# fpga_gtp.net
KiCad netlist of a schematic drawn in Altium Designer
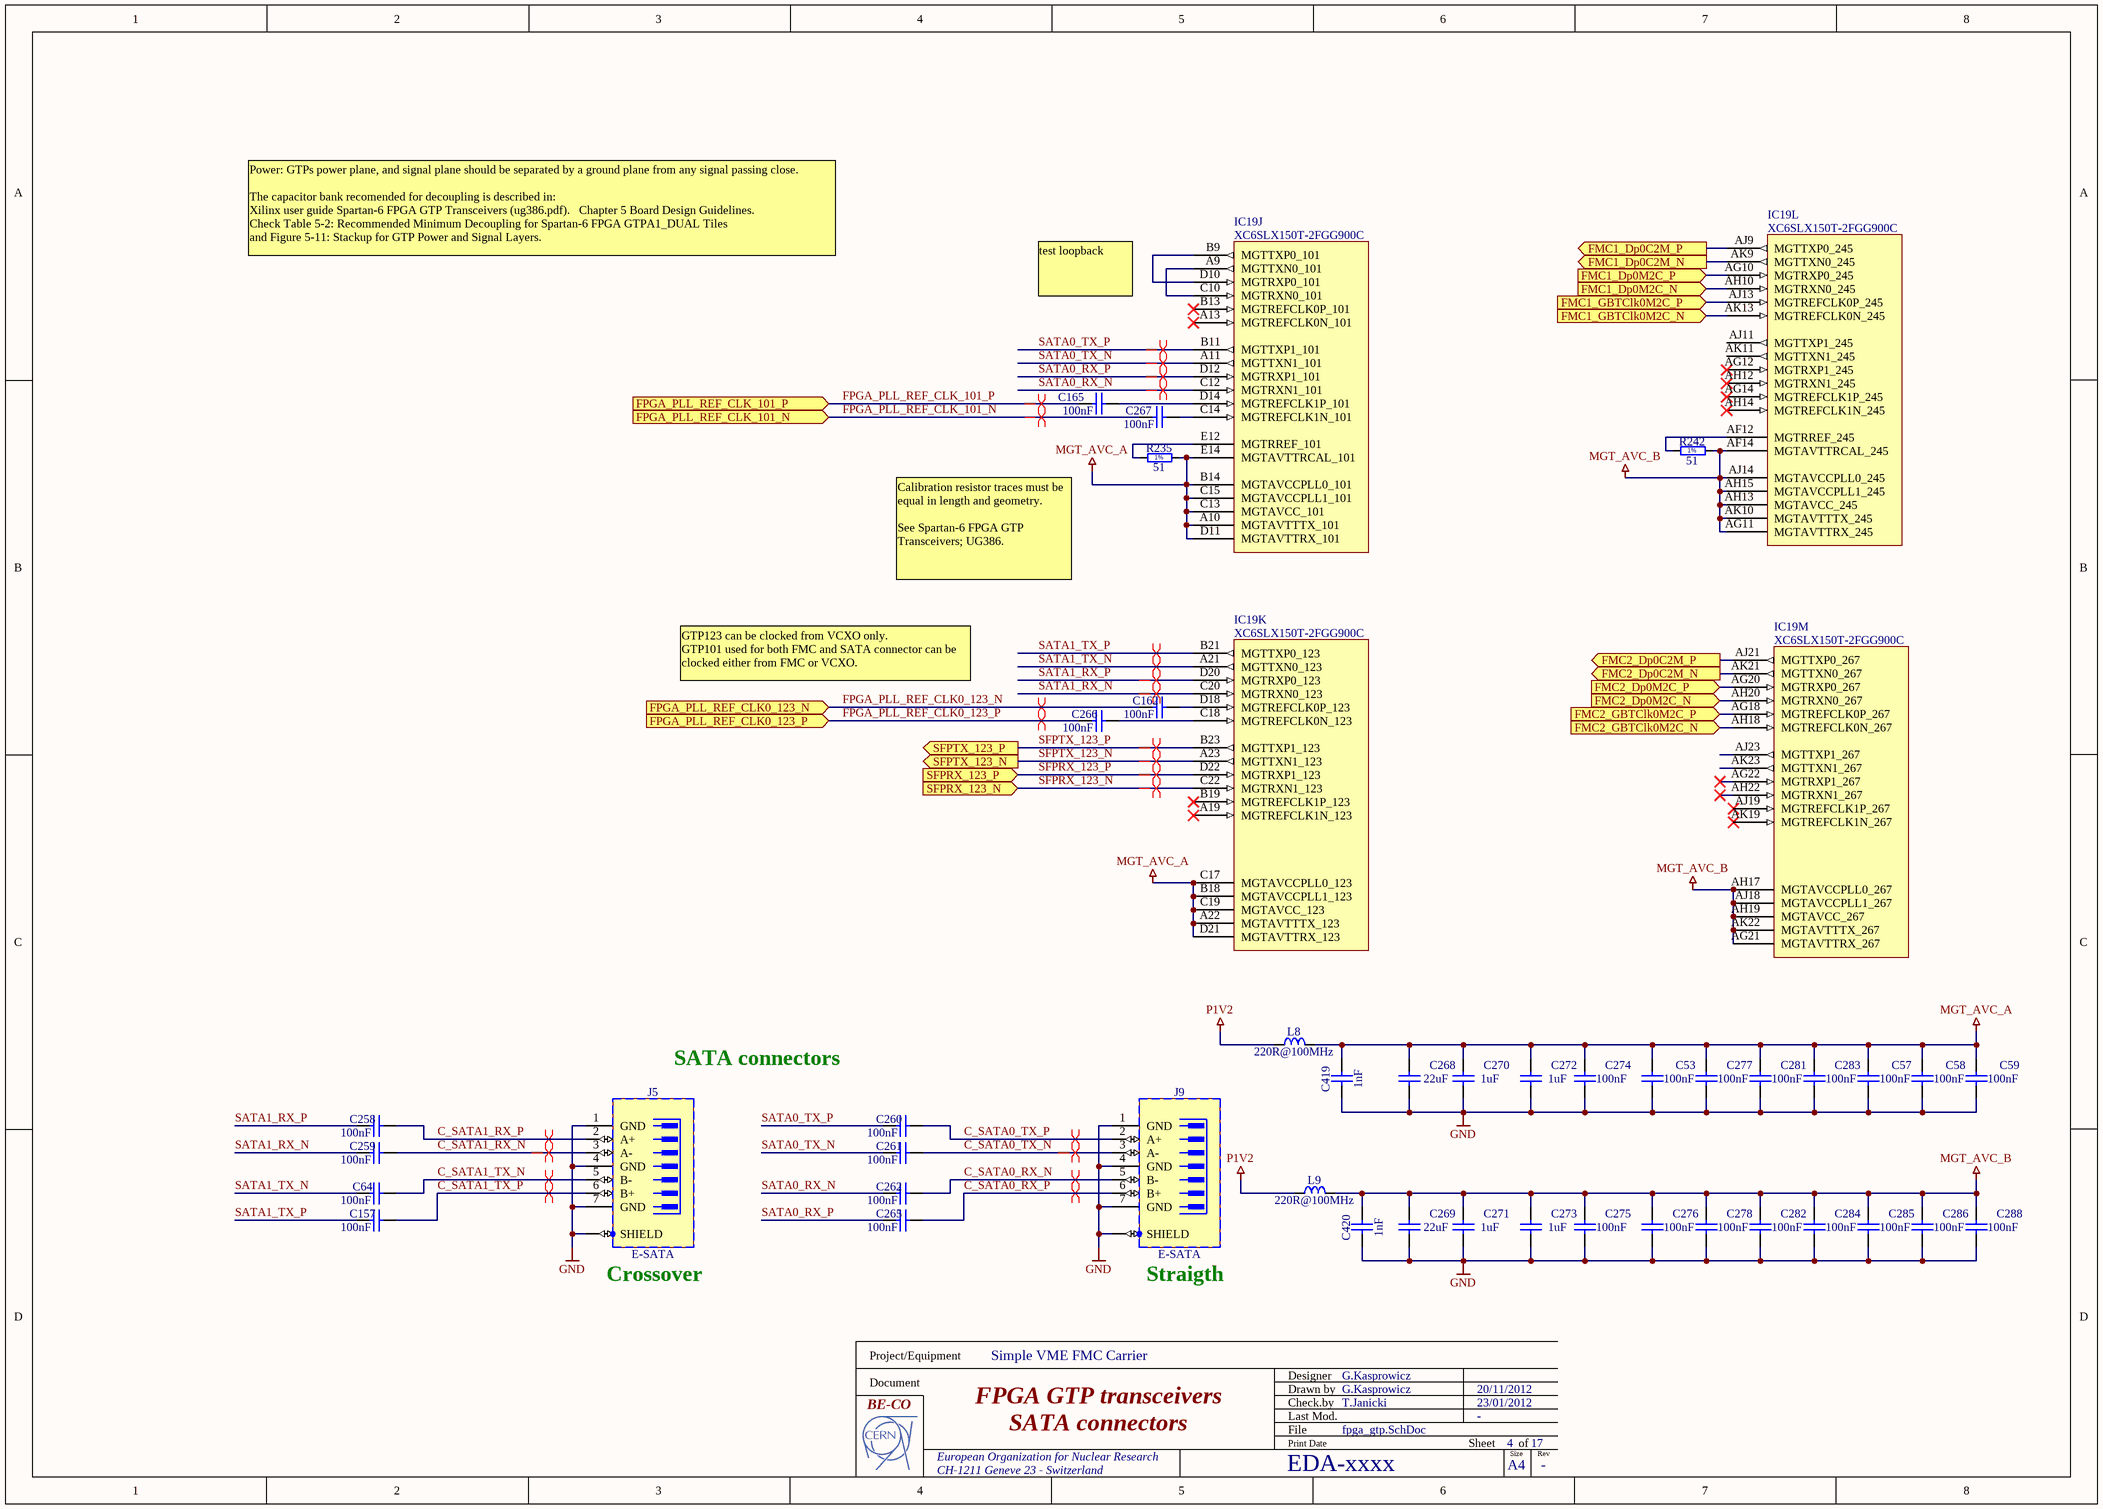
[diagram p0: fpga_gtp.SchDoc]

(export (version "E")
  (design (tool "Eeschema 10.0.6"))
  (components
    (comp (ref "C53")
      (value "100nF")
      (footprint "CAPC1005X55N")
      (description "Non-polarised capacitor")
      (fields
        (field (name "PART NUMBER") "CC0402_100NF_16V_10%_X7R")
        (field (name "VOLTAGE") "16V")
        (field (name "AUTHOR") "CERN DEM JLC")
      )
      (libsource (lib "Capacitors") (part "Capacitor - non polarized"))
    )
    (comp (ref "C57")
      (value "100nF")
      (footprint "CAPC1005X55N")
      (description "Non-polarised capacitor")
      (fields
        (field (name "PART NUMBER") "CC0402_100NF_16V_10%_X7R")
        (field (name "VOLTAGE") "16V")
        (field (name "AUTHOR") "CERN DEM JLC")
      )
      (libsource (lib "Capacitors") (part "Capacitor - non polarized"))
    )
    (comp (ref "C58")
      (value "100nF")
      (footprint "CAPC1005X55N")
      (description "Non-polarised capacitor")
      (fields
        (field (name "PART NUMBER") "CC0402_100NF_16V_10%_X7R")
        (field (name "VOLTAGE") "16V")
        (field (name "AUTHOR") "CERN DEM JLC")
      )
      (libsource (lib "Capacitors") (part "Capacitor - non polarized"))
    )
    (comp (ref "C59")
      (value "100nF")
      (footprint "CAPC1005X55N")
      (description "Non-polarised capacitor")
      (fields
        (field (name "PART NUMBER") "CC0402_100NF_16V_10%_X7R")
        (field (name "VOLTAGE") "16V")
        (field (name "AUTHOR") "CERN DEM JLC")
      )
      (libsource (lib "Capacitors") (part "Capacitor - non polarized"))
    )
    (comp (ref "C64")
      (value "100nF")
      (footprint "CAPC1005X55N")
      (description "Non-polarised capacitor")
      (fields
        (field (name "PART NUMBER") "CC0402_100NF_16V_10%_X7R")
        (field (name "VOLTAGE") "16V")
        (field (name "AUTHOR") "CERN DEM JLC")
      )
      (libsource (lib "Capacitors") (part "Capacitor - non polarized"))
    )
    (comp (ref "C157")
      (value "100nF")
      (footprint "CAPC1005X55N")
      (description "Non-polarised capacitor")
      (fields
        (field (name "PART NUMBER") "CC0402_100NF_16V_10%_X7R")
        (field (name "VOLTAGE") "16V")
        (field (name "AUTHOR") "CERN DEM JLC")
      )
      (libsource (lib "Capacitors") (part "Capacitor - non polarized"))
    )
    (comp (ref "C162")
      (value "100nF")
      (footprint "CAPC1005X55N")
      (description "Non-polarised capacitor")
      (fields
        (field (name "PART NUMBER") "CC0402_100NF_16V_10%_X7R")
        (field (name "VOLTAGE") "16V")
        (field (name "AUTHOR") "CERN DEM JLC")
      )
      (libsource (lib "Capacitors") (part "Capacitor - non polarized"))
    )
    (comp (ref "C165")
      (value "100nF")
      (footprint "CAPC1005X55N")
      (description "Non-polarised capacitor")
      (fields
        (field (name "PART NUMBER") "CC0402_100NF_16V_10%_X7R")
        (field (name "VOLTAGE") "16V")
        (field (name "AUTHOR") "CERN DEM JLC")
      )
      (libsource (lib "Capacitors") (part "Capacitor - non polarized"))
    )
    (comp (ref "C258")
      (value "100nF")
      (footprint "CAPC1005X55N")
      (description "Non-polarised capacitor")
      (fields
        (field (name "PART NUMBER") "CC0402_100NF_16V_10%_X7R")
        (field (name "VOLTAGE") "16V")
        (field (name "AUTHOR") "CERN DEM JLC")
      )
      (libsource (lib "Capacitors") (part "Capacitor - non polarized"))
    )
    (comp (ref "C259")
      (value "100nF")
      (footprint "CAPC1005X55N")
      (description "Non-polarised capacitor")
      (fields
        (field (name "PART NUMBER") "CC0402_100NF_16V_10%_X7R")
        (field (name "VOLTAGE") "16V")
        (field (name "AUTHOR") "CERN DEM JLC")
      )
      (libsource (lib "Capacitors") (part "Capacitor - non polarized"))
    )
    (comp (ref "C260")
      (value "100nF")
      (footprint "CAPC1005X55N")
      (description "Non-polarised capacitor")
      (fields
        (field (name "PART NUMBER") "CC0402_100NF_16V_10%_X7R")
        (field (name "VOLTAGE") "16V")
        (field (name "AUTHOR") "CERN DEM JLC")
      )
      (libsource (lib "Capacitors") (part "Capacitor - non polarized"))
    )
    (comp (ref "C261")
      (value "100nF")
      (footprint "CAPC1005X55N")
      (description "Non-polarised capacitor")
      (fields
        (field (name "PART NUMBER") "CC0402_100NF_16V_10%_X7R")
        (field (name "VOLTAGE") "16V")
        (field (name "AUTHOR") "CERN DEM JLC")
      )
      (libsource (lib "Capacitors") (part "Capacitor - non polarized"))
    )
    (comp (ref "C262")
      (value "100nF")
      (footprint "CAPC1005X55N")
      (description "Non-polarised capacitor")
      (fields
        (field (name "PART NUMBER") "CC0402_100NF_16V_10%_X7R")
        (field (name "VOLTAGE") "16V")
        (field (name "AUTHOR") "CERN DEM JLC")
      )
      (libsource (lib "Capacitors") (part "Capacitor - non polarized"))
    )
    (comp (ref "C265")
      (value "100nF")
      (footprint "CAPC1005X55N")
      (description "Non-polarised capacitor")
      (fields
        (field (name "PART NUMBER") "CC0402_100NF_16V_10%_X7R")
        (field (name "VOLTAGE") "16V")
        (field (name "AUTHOR") "CERN DEM JLC")
      )
      (libsource (lib "Capacitors") (part "Capacitor - non polarized"))
    )
    (comp (ref "C266")
      (value "100nF")
      (footprint "CAPC1005X55N")
      (description "Non-polarised capacitor")
      (fields
        (field (name "PART NUMBER") "CC0402_100NF_16V_10%_X7R")
        (field (name "VOLTAGE") "16V")
        (field (name "AUTHOR") "CERN DEM JLC")
      )
      (libsource (lib "Capacitors") (part "Capacitor - non polarized"))
    )
    (comp (ref "C267")
      (value "100nF")
      (footprint "CAPC1005X55N")
      (description "Non-polarised capacitor")
      (fields
        (field (name "PART NUMBER") "CC0402_100NF_16V_10%_X7R")
        (field (name "VOLTAGE") "16V")
        (field (name "AUTHOR") "CERN DEM JLC")
      )
      (libsource (lib "Capacitors") (part "Capacitor - non polarized"))
    )
    (comp (ref "C268")
      (value "22uF")
      (footprint "CAPC3216X180N")
      (description "Non-polarised capacitor")
      (fields
        (field (name "PART NUMBER") "CC1206_22UF_10V_10%_X7R")
        (field (name "VOLTAGE") "10V")
        (field (name "AUTHOR") "CERN DEM JLC")
      )
      (libsource (lib "Capacitors") (part "Capacitor - non polarized"))
    )
    (comp (ref "C269")
      (value "22uF")
      (footprint "CAPC3216X180N")
      (description "Non-polarised capacitor")
      (fields
        (field (name "PART NUMBER") "CC1206_22UF_10V_10%_X7R")
        (field (name "VOLTAGE") "10V")
        (field (name "AUTHOR") "CERN DEM JLC")
      )
      (libsource (lib "Capacitors") (part "Capacitor - non polarized"))
    )
    (comp (ref "C270")
      (value "1uF")
      (footprint "CAPC1608X87N")
      (description "Non-polarised capacitor")
      (fields
        (field (name "PART NUMBER") "CC0603_1UF_16V_10%_X7R")
        (field (name "VOLTAGE") "16V")
        (field (name "AUTHOR") "CERN DEM JLC")
      )
      (libsource (lib "Capacitors") (part "Capacitor - non polarized"))
    )
    (comp (ref "C271")
      (value "1uF")
      (footprint "CAPC1608X87N")
      (description "Non-polarised capacitor")
      (fields
        (field (name "PART NUMBER") "CC0603_1UF_16V_10%_X7R")
        (field (name "VOLTAGE") "16V")
        (field (name "AUTHOR") "CERN DEM JLC")
      )
      (libsource (lib "Capacitors") (part "Capacitor - non polarized"))
    )
    (comp (ref "C272")
      (value "1uF")
      (footprint "CAPC1608X87N")
      (description "Non-polarised capacitor")
      (fields
        (field (name "PART NUMBER") "CC0603_1UF_16V_10%_X7R")
        (field (name "VOLTAGE") "16V")
        (field (name "AUTHOR") "CERN DEM JLC")
      )
      (libsource (lib "Capacitors") (part "Capacitor - non polarized"))
    )
    (comp (ref "C273")
      (value "1uF")
      (footprint "CAPC1608X87N")
      (description "Non-polarised capacitor")
      (fields
        (field (name "PART NUMBER") "CC0603_1UF_16V_10%_X7R")
        (field (name "VOLTAGE") "16V")
        (field (name "AUTHOR") "CERN DEM JLC")
      )
      (libsource (lib "Capacitors") (part "Capacitor - non polarized"))
    )
    (comp (ref "C274")
      (value "100nF")
      (footprint "CAPC1005X55N")
      (description "Non-polarised capacitor")
      (fields
        (field (name "PART NUMBER") "CC0402_100NF_16V_10%_X7R")
        (field (name "VOLTAGE") "16V")
        (field (name "AUTHOR") "CERN DEM JLC")
      )
      (libsource (lib "Capacitors") (part "Capacitor - non polarized"))
    )
    (comp (ref "C275")
      (value "100nF")
      (footprint "CAPC1005X55N")
      (description "Non-polarised capacitor")
      (fields
        (field (name "PART NUMBER") "CC0402_100NF_16V_10%_X7R")
        (field (name "VOLTAGE") "16V")
        (field (name "AUTHOR") "CERN DEM JLC")
      )
      (libsource (lib "Capacitors") (part "Capacitor - non polarized"))
    )
    (comp (ref "C276")
      (value "100nF")
      (footprint "CAPC1005X55N")
      (description "Non-polarised capacitor")
      (fields
        (field (name "PART NUMBER") "CC0402_100NF_16V_10%_X7R")
        (field (name "VOLTAGE") "16V")
        (field (name "AUTHOR") "CERN DEM JLC")
      )
      (libsource (lib "Capacitors") (part "Capacitor - non polarized"))
    )
    (comp (ref "C277")
      (value "100nF")
      (footprint "CAPC1005X55N")
      (description "Non-polarised capacitor")
      (fields
        (field (name "PART NUMBER") "CC0402_100NF_16V_10%_X7R")
        (field (name "VOLTAGE") "16V")
        (field (name "AUTHOR") "CERN DEM JLC")
      )
      (libsource (lib "Capacitors") (part "Capacitor - non polarized"))
    )
    (comp (ref "C278")
      (value "100nF")
      (footprint "CAPC1005X55N")
      (description "Non-polarised capacitor")
      (fields
        (field (name "PART NUMBER") "CC0402_100NF_16V_10%_X7R")
        (field (name "VOLTAGE") "16V")
        (field (name "AUTHOR") "CERN DEM JLC")
      )
      (libsource (lib "Capacitors") (part "Capacitor - non polarized"))
    )
    (comp (ref "C281")
      (value "100nF")
      (footprint "CAPC1005X55N")
      (description "Non-polarised capacitor")
      (fields
        (field (name "PART NUMBER") "CC0402_100NF_16V_10%_X7R")
        (field (name "VOLTAGE") "16V")
        (field (name "AUTHOR") "CERN DEM JLC")
      )
      (libsource (lib "Capacitors") (part "Capacitor - non polarized"))
    )
    (comp (ref "C282")
      (value "100nF")
      (footprint "CAPC1005X55N")
      (description "Non-polarised capacitor")
      (fields
        (field (name "PART NUMBER") "CC0402_100NF_16V_10%_X7R")
        (field (name "VOLTAGE") "16V")
        (field (name "AUTHOR") "CERN DEM JLC")
      )
      (libsource (lib "Capacitors") (part "Capacitor - non polarized"))
    )
    (comp (ref "C283")
      (value "100nF")
      (footprint "CAPC1005X55N")
      (description "Non-polarised capacitor")
      (fields
        (field (name "PART NUMBER") "CC0402_100NF_16V_10%_X7R")
        (field (name "VOLTAGE") "16V")
        (field (name "AUTHOR") "CERN DEM JLC")
      )
      (libsource (lib "Capacitors") (part "Capacitor - non polarized"))
    )
    (comp (ref "C284")
      (value "100nF")
      (footprint "CAPC1005X55N")
      (description "Non-polarised capacitor")
      (fields
        (field (name "PART NUMBER") "CC0402_100NF_16V_10%_X7R")
        (field (name "VOLTAGE") "16V")
        (field (name "AUTHOR") "CERN DEM JLC")
      )
      (libsource (lib "Capacitors") (part "Capacitor - non polarized"))
    )
    (comp (ref "C285")
      (value "100nF")
      (footprint "CAPC1005X55N")
      (description "Non-polarised capacitor")
      (fields
        (field (name "PART NUMBER") "CC0402_100NF_16V_10%_X7R")
        (field (name "VOLTAGE") "16V")
        (field (name "AUTHOR") "CERN DEM JLC")
      )
      (libsource (lib "Capacitors") (part "Capacitor - non polarized"))
    )
    (comp (ref "C286")
      (value "100nF")
      (footprint "CAPC1005X55N")
      (description "Non-polarised capacitor")
      (fields
        (field (name "PART NUMBER") "CC0402_100NF_16V_10%_X7R")
        (field (name "VOLTAGE") "16V")
        (field (name "AUTHOR") "CERN DEM JLC")
      )
      (libsource (lib "Capacitors") (part "Capacitor - non polarized"))
    )
    (comp (ref "C288")
      (value "100nF")
      (footprint "CAPC1005X55N")
      (description "Non-polarised capacitor")
      (fields
        (field (name "PART NUMBER") "CC0402_100NF_16V_10%_X7R")
        (field (name "VOLTAGE") "16V")
        (field (name "AUTHOR") "CERN DEM JLC")
      )
      (libsource (lib "Capacitors") (part "Capacitor - non polarized"))
    )
    (comp (ref "C419")
      (value "1nF")
      (footprint "CAPC1005X55N")
      (description "Non-polarised capacitor")
      (fields
        (field (name "PART NUMBER") "CC0402_1NF_50V_10%_X7R")
        (field (name "VOLTAGE") "50V")
        (field (name "AUTHOR") "CERN DEM JLC")
      )
      (libsource (lib "Capacitors") (part "Capacitor - non polarized"))
    )
    (comp (ref "C420")
      (value "1nF")
      (footprint "CAPC1005X55N")
      (description "Non-polarised capacitor")
      (fields
        (field (name "PART NUMBER") "CC0402_1NF_50V_10%_X7R")
        (field (name "VOLTAGE") "50V")
        (field (name "AUTHOR") "CERN DEM JLC")
      )
      (libsource (lib "Capacitors") (part "Capacitor - non polarized"))
    )
    (comp (ref "IC19")
      (value "XC6SLX150T-2FGG900C")
      (footprint "BGA900C100P30X30_3100X3100X260")
      (description "SPARTAN-6, FPGA, 900-Ball BGA, Commercial Grade, Pb-Free")
      (fields (field (name "MANUFACTURER") "XILINX") (field (name "AUTHOR") "CERN DEM JLC"))
      (libsource (lib "ICs And Semiconductors") (part "XC6SLX150T-2FGG900C"))
    )
    (comp (ref "J5")
      (value "E-SATA")
      (footprint "FCI_10074141-001LF")
      (description "7 Pin + 1 Shield SATA Receptacle")
      (fields
        (field (name "PART NUMBER") "FCI_10074141-001LF")
        (field (name "MANUFACTURER") "FCI")
        (field (name "AUTHOR") "CERN DEM JLC")
      )
      (libsource (lib "Connectors") (part "Connector SATA 7 Male + 1 Shield"))
    )
    (comp (ref "J9")
      (value "E-SATA")
      (footprint "FCI_10074141-001LF")
      (description "7 Pin + 1 Shield SATA Receptacle")
      (fields
        (field (name "PART NUMBER") "FCI_10074141-001LF")
        (field (name "MANUFACTURER") "FCI")
        (field (name "AUTHOR") "CERN DEM JLC")
      )
      (libsource (lib "Connectors") (part "Connector SATA 7 Male + 1 Shield"))
    )
    (comp (ref "L8")
      (value "220R@100MHz")
      (footprint "INDC2012X105N")
      (description "Inductor")
      (fields
        (field (name "PART NUMBER") "IND0805_MURATA_BLM21PG221SN1D")
        (field (name "POWER") "2A")
        (field (name "AUTHOR") "CERN DEM JLC")
      )
      (libsource (lib "Inductors & Transformers") (part "Inductor"))
    )
    (comp (ref "L9")
      (value "220R@100MHz")
      (footprint "INDC2012X105N")
      (description "Inductor")
      (fields
        (field (name "PART NUMBER") "IND0805_MURATA_BLM21PG221SN1D")
        (field (name "POWER") "2A")
        (field (name "AUTHOR") "CERN DEM JLC")
      )
      (libsource (lib "Inductors & Transformers") (part "Inductor"))
    )
    (comp (ref "R235")
      (value "51")
      (footprint "RESC1005X40N")
      (description "Resistor - 1%")
      (fields
        (field (name "PART NUMBER") "R0402_51R_1%_0.0625W_100PPM")
        (field (name "POWER") "0.0625W")
        (field (name "AUTHOR") "CERN DEM JLC")
      )
      (libsource (lib "Resistors") (part "Resistor - 1%"))
    )
    (comp (ref "R242")
      (value "51")
      (footprint "RESC1005X40N")
      (description "Resistor - 1%")
      (fields
        (field (name "PART NUMBER") "R0402_51R_1%_0.0625W_100PPM")
        (field (name "POWER") "0.0625W")
        (field (name "AUTHOR") "CERN DEM JLC")
      )
      (libsource (lib "Resistors") (part "Resistor - 1%"))
    )
  )
  (nets
    (net (code "1") (name "/C_SATA0_RX_N") (class "Default")
      (node (ref "C262") (pin "2") (pinfunction "2_2") (pintype "passive"))
      (node (ref "J9") (pin "5") (pinfunction "B-_5") (pintype "bidirectional"))
    )
    (net (code "2") (name "/C_SATA0_RX_P") (class "Default")
      (node (ref "C265") (pin "2") (pinfunction "2_2") (pintype "passive"))
      (node (ref "J9") (pin "6") (pinfunction "B+_6") (pintype "bidirectional"))
    )
    (net (code "3") (name "/C_SATA0_TX_N") (class "Default")
      (node (ref "C261") (pin "2") (pinfunction "2_2") (pintype "passive"))
      (node (ref "J9") (pin "3") (pinfunction "A-_3") (pintype "bidirectional"))
    )
    (net (code "4") (name "/C_SATA0_TX_P") (class "Default")
      (node (ref "C260") (pin "2") (pinfunction "2_2") (pintype "passive"))
      (node (ref "J9") (pin "2") (pinfunction "A+_2") (pintype "bidirectional"))
    )
    (net (code "5") (name "/C_SATA1_RX_N") (class "Default")
      (node (ref "C259") (pin "2") (pinfunction "2_2") (pintype "passive"))
      (node (ref "J5") (pin "3") (pinfunction "A-_3") (pintype "bidirectional"))
    )
    (net (code "6") (name "/C_SATA1_RX_P") (class "Default")
      (node (ref "C258") (pin "2") (pinfunction "2_2") (pintype "passive"))
      (node (ref "J5") (pin "2") (pinfunction "A+_2") (pintype "bidirectional"))
    )
    (net (code "7") (name "/C_SATA1_TX_N") (class "Default")
      (node (ref "C64") (pin "2") (pinfunction "2_2") (pintype "passive"))
      (node (ref "J5") (pin "5") (pinfunction "B-_5") (pintype "bidirectional"))
    )
    (net (code "8") (name "/C_SATA1_TX_P") (class "Default")
      (node (ref "C157") (pin "2") (pinfunction "2_2") (pintype "passive"))
      (node (ref "J5") (pin "6") (pinfunction "B+_6") (pintype "bidirectional"))
    )
    (net (code "9") (name "/FMC1_Dp0C2M_N") (class "Default")
      (node (ref "IC19") (pin "AK9") (pinfunction "MGTTXN0_245_AK9") (pintype "output"))
    )
    (net (code "10") (name "/FMC1_Dp0C2M_P") (class "Default")
      (node (ref "IC19") (pin "AJ9") (pinfunction "MGTTXP0_245_AJ9") (pintype "output"))
    )
    (net (code "11") (name "/FMC1_Dp0M2C_N") (class "Default")
      (node (ref "IC19") (pin "AH10") (pinfunction "MGTRXN0_245_AH10") (pintype "input"))
    )
    (net (code "12") (name "/FMC1_Dp0M2C_P") (class "Default")
      (node (ref "IC19") (pin "AG10") (pinfunction "MGTRXP0_245_AG10") (pintype "input"))
    )
    (net (code "13") (name "/FMC1_GBTClk0M2C_N") (class "Default")
      (node (ref "IC19") (pin "AK13") (pinfunction "MGTREFCLK0N_245_AK13") (pintype "input"))
    )
    (net (code "14") (name "/FMC1_GBTClk0M2C_P") (class "Default")
      (node (ref "IC19") (pin "AJ13") (pinfunction "MGTREFCLK0P_245_AJ13") (pintype "input"))
    )
    (net (code "15") (name "/FMC2_Dp0C2M_N") (class "Default")
      (node (ref "IC19") (pin "AK21") (pinfunction "MGTTXN0_267_AK21") (pintype "output"))
    )
    (net (code "16") (name "/FMC2_Dp0C2M_P") (class "Default")
      (node (ref "IC19") (pin "AJ21") (pinfunction "MGTTXP0_267_AJ21") (pintype "output"))
    )
    (net (code "17") (name "/FMC2_Dp0M2C_N") (class "Default")
      (node (ref "IC19") (pin "AH20") (pinfunction "MGTRXN0_267_AH20") (pintype "input"))
    )
    (net (code "18") (name "/FMC2_Dp0M2C_P") (class "Default")
      (node (ref "IC19") (pin "AG20") (pinfunction "MGTRXP0_267_AG20") (pintype "input"))
    )
    (net (code "19") (name "/FMC2_GBTClk0M2C_N") (class "Default")
      (node (ref "IC19") (pin "AH18") (pinfunction "MGTREFCLK0N_267_AH18") (pintype "input"))
    )
    (net (code "20") (name "/FMC2_GBTClk0M2C_P") (class "Default")
      (node (ref "IC19") (pin "AG18") (pinfunction "MGTREFCLK0P_267_AG18") (pintype "input"))
    )
    (net (code "21") (name "/FPGA_PLL_REF_CLK0_123_N") (class "Default")
      (node (ref "C162") (pin "1") (pinfunction "1_1") (pintype "passive"))
    )
    (net (code "22") (name "/FPGA_PLL_REF_CLK0_123_P") (class "Default")
      (node (ref "C266") (pin "1") (pinfunction "1_1") (pintype "passive"))
    )
    (net (code "23") (name "/FPGA_PLL_REF_CLK_101_N") (class "Default")
      (node (ref "C267") (pin "1") (pinfunction "1_1") (pintype "passive"))
    )
    (net (code "24") (name "/FPGA_PLL_REF_CLK_101_P") (class "Default")
      (node (ref "C165") (pin "1") (pinfunction "1_1") (pintype "passive"))
    )
    (net (code "25") (name "/SATA0_RX_N") (class "Default")
      (node (ref "C262") (pin "1") (pinfunction "1_1") (pintype "passive"))
      (node (ref "IC19") (pin "C12") (pinfunction "MGTRXN1_101_C12") (pintype "input"))
    )
    (net (code "26") (name "/SATA0_RX_P") (class "Default")
      (node (ref "C265") (pin "1") (pinfunction "1_1") (pintype "passive"))
      (node (ref "IC19") (pin "D12") (pinfunction "MGTRXP1_101_D12") (pintype "input"))
    )
    (net (code "27") (name "/SATA0_TX_N") (class "Default")
      (node (ref "C261") (pin "1") (pinfunction "1_1") (pintype "passive"))
      (node (ref "IC19") (pin "A11") (pinfunction "MGTTXN1_101_A11") (pintype "output"))
    )
    (net (code "28") (name "/SATA0_TX_P") (class "Default")
      (node (ref "C260") (pin "1") (pinfunction "1_1") (pintype "passive"))
      (node (ref "IC19") (pin "B11") (pinfunction "MGTTXP1_101_B11") (pintype "output"))
    )
    (net (code "29") (name "/SATA1_RX_N") (class "Default")
      (node (ref "C259") (pin "1") (pinfunction "1_1") (pintype "passive"))
      (node (ref "IC19") (pin "C20") (pinfunction "MGTRXN0_123_C20") (pintype "input"))
    )
    (net (code "30") (name "/SATA1_RX_P") (class "Default")
      (node (ref "C258") (pin "1") (pinfunction "1_1") (pintype "passive"))
      (node (ref "IC19") (pin "D20") (pinfunction "MGTRXP0_123_D20") (pintype "input"))
    )
    (net (code "31") (name "/SATA1_TX_N") (class "Default")
      (node (ref "C64") (pin "1") (pinfunction "1_1") (pintype "passive"))
      (node (ref "IC19") (pin "A21") (pinfunction "MGTTXN0_123_A21") (pintype "output"))
    )
    (net (code "32") (name "/SATA1_TX_P") (class "Default")
      (node (ref "C157") (pin "1") (pinfunction "1_1") (pintype "passive"))
      (node (ref "IC19") (pin "B21") (pinfunction "MGTTXP0_123_B21") (pintype "output"))
    )
    (net (code "33") (name "/SFPRX_123_N") (class "Default")
      (node (ref "IC19") (pin "C22") (pinfunction "MGTRXN1_123_C22") (pintype "input"))
    )
    (net (code "34") (name "/SFPRX_123_P") (class "Default")
      (node (ref "IC19") (pin "D22") (pinfunction "MGTRXP1_123_D22") (pintype "input"))
    )
    (net (code "35") (name "/SFPTX_123_N") (class "Default")
      (node (ref "IC19") (pin "A23") (pinfunction "MGTTXN1_123_A23") (pintype "output"))
    )
    (net (code "36") (name "/SFPTX_123_P") (class "Default")
      (node (ref "IC19") (pin "B23") (pinfunction "MGTTXP1_123_B23") (pintype "output"))
    )
    (net (code "37") (name "GND") (class "Default")
      (node (ref "C268") (pin "1") (pinfunction "1_1") (pintype "passive"))
      (node (ref "C269") (pin "1") (pinfunction "1_1") (pintype "passive"))
      (node (ref "C270") (pin "1") (pinfunction "1_1") (pintype "passive"))
      (node (ref "C271") (pin "1") (pinfunction "1_1") (pintype "passive"))
      (node (ref "C272") (pin "1") (pinfunction "1_1") (pintype "passive"))
      (node (ref "C273") (pin "1") (pinfunction "1_1") (pintype "passive"))
      (node (ref "C274") (pin "1") (pinfunction "1_1") (pintype "passive"))
      (node (ref "C275") (pin "1") (pinfunction "1_1") (pintype "passive"))
      (node (ref "C276") (pin "1") (pinfunction "1_1") (pintype "passive"))
      (node (ref "C277") (pin "1") (pinfunction "1_1") (pintype "passive"))
      (node (ref "C278") (pin "1") (pinfunction "1_1") (pintype "passive"))
      (node (ref "C281") (pin "1") (pinfunction "1_1") (pintype "passive"))
      (node (ref "C282") (pin "1") (pinfunction "1_1") (pintype "passive"))
      (node (ref "C283") (pin "1") (pinfunction "1_1") (pintype "passive"))
      (node (ref "C284") (pin "1") (pinfunction "1_1") (pintype "passive"))
      (node (ref "C285") (pin "1") (pinfunction "1_1") (pintype "passive"))
      (node (ref "C286") (pin "1") (pinfunction "1_1") (pintype "passive"))
      (node (ref "C288") (pin "1") (pinfunction "1_1") (pintype "passive"))
      (node (ref "C419") (pin "1") (pinfunction "1_1") (pintype "passive"))
      (node (ref "C420") (pin "1") (pinfunction "1_1") (pintype "passive"))
      (node (ref "C53") (pin "1") (pinfunction "1_1") (pintype "passive"))
      (node (ref "C57") (pin "1") (pinfunction "1_1") (pintype "passive"))
      (node (ref "C58") (pin "1") (pinfunction "1_1") (pintype "passive"))
      (node (ref "C59") (pin "1") (pinfunction "1_1") (pintype "passive"))
      (node (ref "J5") (pin "1") (pinfunction "GND_1") (pintype "power_in"))
      (node (ref "J5") (pin "4") (pinfunction "GND_4") (pintype "power_in"))
      (node (ref "J5") (pin "7") (pinfunction "GND_7") (pintype "power_in"))
      (node (ref "J5") (pin "8") (pinfunction "SHIELD_8") (pintype "bidirectional"))
      (node (ref "J9") (pin "1") (pinfunction "GND_1") (pintype "power_in"))
      (node (ref "J9") (pin "4") (pinfunction "GND_4") (pintype "power_in"))
      (node (ref "J9") (pin "7") (pinfunction "GND_7") (pintype "power_in"))
      (node (ref "J9") (pin "8") (pinfunction "SHIELD_8") (pintype "bidirectional"))
    )
    (net (code "38") (name "MGT_AVC_A") (class "Default")
      (node (ref "C268") (pin "2") (pinfunction "2_2") (pintype "passive"))
      (node (ref "C270") (pin "2") (pinfunction "2_2") (pintype "passive"))
      (node (ref "C272") (pin "2") (pinfunction "2_2") (pintype "passive"))
      (node (ref "C274") (pin "2") (pinfunction "2_2") (pintype "passive"))
      (node (ref "C277") (pin "2") (pinfunction "2_2") (pintype "passive"))
      (node (ref "C281") (pin "2") (pinfunction "2_2") (pintype "passive"))
      (node (ref "C283") (pin "2") (pinfunction "2_2") (pintype "passive"))
      (node (ref "C419") (pin "2") (pinfunction "2_2") (pintype "passive"))
      (node (ref "C53") (pin "2") (pinfunction "2_2") (pintype "passive"))
      (node (ref "C57") (pin "2") (pinfunction "2_2") (pintype "passive"))
      (node (ref "C58") (pin "2") (pinfunction "2_2") (pintype "passive"))
      (node (ref "C59") (pin "2") (pinfunction "2_2") (pintype "passive"))
      (node (ref "IC19") (pin "A10") (pinfunction "MGTAVTTTX_101_A10") (pintype "power_in"))
      (node (ref "IC19") (pin "A22") (pinfunction "MGTAVTTTX_123_A22") (pintype "power_in"))
      (node (ref "IC19") (pin "B14") (pinfunction "MGTAVCCPLL0_101_B14") (pintype "power_in"))
      (node (ref "IC19") (pin "B18") (pinfunction "MGTAVCCPLL1_123_B18") (pintype "power_in"))
      (node (ref "IC19") (pin "C13") (pinfunction "MGTAVCC_101_C13") (pintype "power_in"))
      (node (ref "IC19") (pin "C15") (pinfunction "MGTAVCCPLL1_101_C15") (pintype "power_in"))
      (node (ref "IC19") (pin "C17") (pinfunction "MGTAVCCPLL0_123_C17") (pintype "power_in"))
      (node (ref "IC19") (pin "C19") (pinfunction "MGTAVCC_123_C19") (pintype "power_in"))
      (node (ref "IC19") (pin "D11") (pinfunction "MGTAVTTRX_101_D11") (pintype "power_in"))
      (node (ref "IC19") (pin "D21") (pinfunction "MGTAVTTRX_123_D21") (pintype "power_in"))
      (node (ref "IC19") (pin "E14") (pinfunction "MGTAVTTRCAL_101_E14") (pintype "power_in"))
      (node (ref "L8") (pin "2") (pinfunction "2_2") (pintype "passive"))
      (node (ref "R235") (pin "2") (pinfunction "2_2") (pintype "passive"))
    )
    (net (code "39") (name "MGT_AVC_B") (class "Default")
      (node (ref "C269") (pin "2") (pinfunction "2_2") (pintype "passive"))
      (node (ref "C271") (pin "2") (pinfunction "2_2") (pintype "passive"))
      (node (ref "C273") (pin "2") (pinfunction "2_2") (pintype "passive"))
      (node (ref "C275") (pin "2") (pinfunction "2_2") (pintype "passive"))
      (node (ref "C276") (pin "2") (pinfunction "2_2") (pintype "passive"))
      (node (ref "C278") (pin "2") (pinfunction "2_2") (pintype "passive"))
      (node (ref "C282") (pin "2") (pinfunction "2_2") (pintype "passive"))
      (node (ref "C284") (pin "2") (pinfunction "2_2") (pintype "passive"))
      (node (ref "C285") (pin "2") (pinfunction "2_2") (pintype "passive"))
      (node (ref "C286") (pin "2") (pinfunction "2_2") (pintype "passive"))
      (node (ref "C288") (pin "2") (pinfunction "2_2") (pintype "passive"))
      (node (ref "C420") (pin "2") (pinfunction "2_2") (pintype "passive"))
      (node (ref "IC19") (pin "AF14") (pinfunction "MGTAVTTRCAL_245_AF14") (pintype "power_in"))
      (node (ref "IC19") (pin "AG11") (pinfunction "MGTAVTTRX_245_AG11") (pintype "power_in"))
      (node (ref "IC19") (pin "AG21") (pinfunction "MGTAVTTRX_267_AG21") (pintype "power_in"))
      (node (ref "IC19") (pin "AH13") (pinfunction "MGTAVCC_245_AH13") (pintype "power_in"))
      (node (ref "IC19") (pin "AH15") (pinfunction "MGTAVCCPLL1_245_AH15") (pintype "power_in"))
      (node (ref "IC19") (pin "AH17") (pinfunction "MGTAVCCPLL0_267_AH17") (pintype "power_in"))
      (node (ref "IC19") (pin "AH19") (pinfunction "MGTAVCC_267_AH19") (pintype "power_in"))
      (node (ref "IC19") (pin "AJ14") (pinfunction "MGTAVCCPLL0_245_AJ14") (pintype "power_in"))
      (node (ref "IC19") (pin "AJ18") (pinfunction "MGTAVCCPLL1_267_AJ18") (pintype "power_in"))
      (node (ref "IC19") (pin "AK10") (pinfunction "MGTAVTTTX_245_AK10") (pintype "power_in"))
      (node (ref "IC19") (pin "AK22") (pinfunction "MGTAVTTTX_267_AK22") (pintype "power_in"))
      (node (ref "L9") (pin "2") (pinfunction "2_2") (pintype "passive"))
      (node (ref "R242") (pin "2") (pinfunction "2_2") (pintype "passive"))
    )
    (net (code "40") (name "Net-(IC19J-MGTREFCLK1N_101)") (class "Default")
      (node (ref "C267") (pin "2") (pinfunction "2_2") (pintype "passive"))
      (node (ref "IC19") (pin "C14") (pinfunction "MGTREFCLK1N_101_C14") (pintype "input"))
    )
    (net (code "41") (name "Net-(IC19J-MGTREFCLK1P_101)") (class "Default")
      (node (ref "C165") (pin "2") (pinfunction "2_2") (pintype "passive"))
      (node (ref "IC19") (pin "D14") (pinfunction "MGTREFCLK1P_101_D14") (pintype "input"))
    )
    (net (code "42") (name "Net-(IC19J-MGTRREF_101)") (class "Default")
      (node (ref "IC19") (pin "E12") (pinfunction "MGTRREF_101_E12") (pintype "power_in"))
      (node (ref "R235") (pin "1") (pinfunction "1_1") (pintype "passive"))
    )
    (net (code "43") (name "Net-(IC19J-MGTRXN0_101)") (class "Default")
      (node (ref "IC19") (pin "A9") (pinfunction "MGTTXN0_101_A9") (pintype "output"))
      (node (ref "IC19") (pin "C10") (pinfunction "MGTRXN0_101_C10") (pintype "input"))
    )
    (net (code "44") (name "Net-(IC19J-MGTRXP0_101)") (class "Default")
      (node (ref "IC19") (pin "B9") (pinfunction "MGTTXP0_101_B9") (pintype "output"))
      (node (ref "IC19") (pin "D10") (pinfunction "MGTRXP0_101_D10") (pintype "input"))
    )
    (net (code "45") (name "Net-(IC19K-MGTREFCLK0N_123)") (class "Default")
      (node (ref "C266") (pin "2") (pinfunction "2_2") (pintype "passive"))
      (node (ref "IC19") (pin "C18") (pinfunction "MGTREFCLK0N_123_C18") (pintype "input"))
    )
    (net (code "46") (name "Net-(IC19K-MGTREFCLK0P_123)") (class "Default")
      (node (ref "C162") (pin "2") (pinfunction "2_2") (pintype "passive"))
      (node (ref "IC19") (pin "D18") (pinfunction "MGTREFCLK0P_123_D18") (pintype "input"))
    )
    (net (code "47") (name "Net-(IC19L-MGTRREF_245)") (class "Default")
      (node (ref "IC19") (pin "AF12") (pinfunction "MGTRREF_245_AF12") (pintype "power_in"))
      (node (ref "R242") (pin "1") (pinfunction "1_1") (pintype "passive"))
    )
    (net (code "48") (name "P1V2") (class "Default")
      (node (ref "L8") (pin "1") (pinfunction "1_1") (pintype "passive"))
      (node (ref "L9") (pin "1") (pinfunction "1_1") (pintype "passive"))
    )
    (net (code "49") (name "unconnected-(IC19J-MGTREFCLK0N_101-PadA13)") (class "Default")
      (node (ref "IC19") (pin "A13") (pinfunction "MGTREFCLK0N_101_A13") (pintype "input+no_connect"))
    )
    (net (code "50") (name "unconnected-(IC19J-MGTREFCLK0P_101-PadB13)") (class "Default")
      (node (ref "IC19") (pin "B13") (pinfunction "MGTREFCLK0P_101_B13") (pintype "input+no_connect"))
    )
    (net (code "51") (name "unconnected-(IC19K-MGTREFCLK1N_123-PadA19)") (class "Default")
      (node (ref "IC19") (pin "A19") (pinfunction "MGTREFCLK1N_123_A19") (pintype "input+no_connect"))
    )
    (net (code "52") (name "unconnected-(IC19K-MGTREFCLK1P_123-PadB19)") (class "Default")
      (node (ref "IC19") (pin "B19") (pinfunction "MGTREFCLK1P_123_B19") (pintype "input+no_connect"))
    )
    (net (code "53") (name "unconnected-(IC19L-MGTREFCLK1N_245-PadAH14)") (class "Default")
      (node (ref "IC19") (pin "AH14") (pinfunction "MGTREFCLK1N_245_AH14") (pintype "input+no_connect"))
    )
    (net (code "54") (name "unconnected-(IC19L-MGTREFCLK1P_245-PadAG14)") (class "Default")
      (node (ref "IC19") (pin "AG14") (pinfunction "MGTREFCLK1P_245_AG14") (pintype "input+no_connect"))
    )
    (net (code "55") (name "unconnected-(IC19L-MGTRXN1_245-PadAH12)") (class "Default")
      (node (ref "IC19") (pin "AH12") (pinfunction "MGTRXN1_245_AH12") (pintype "input+no_connect"))
    )
    (net (code "56") (name "unconnected-(IC19L-MGTRXP1_245-PadAG12)") (class "Default")
      (node (ref "IC19") (pin "AG12") (pinfunction "MGTRXP1_245_AG12") (pintype "input+no_connect"))
    )
    (net (code "57") (name "unconnected-(IC19L-MGTTXN1_245-PadAK11)") (class "Default")
      (node (ref "IC19") (pin "AK11") (pinfunction "MGTTXN1_245_AK11") (pintype "output"))
    )
    (net (code "58") (name "unconnected-(IC19L-MGTTXP1_245-PadAJ11)") (class "Default")
      (node (ref "IC19") (pin "AJ11") (pinfunction "MGTTXP1_245_AJ11") (pintype "output"))
    )
    (net (code "59") (name "unconnected-(IC19M-MGTREFCLK1N_267-PadAK19)") (class "Default")
      (node (ref "IC19") (pin "AK19") (pinfunction "MGTREFCLK1N_267_AK19") (pintype "input+no_connect"))
    )
    (net (code "60") (name "unconnected-(IC19M-MGTREFCLK1P_267-PadAJ19)") (class "Default")
      (node (ref "IC19") (pin "AJ19") (pinfunction "MGTREFCLK1P_267_AJ19") (pintype "input+no_connect"))
    )
    (net (code "61") (name "unconnected-(IC19M-MGTRXN1_267-PadAH22)") (class "Default")
      (node (ref "IC19") (pin "AH22") (pinfunction "MGTRXN1_267_AH22") (pintype "input+no_connect"))
    )
    (net (code "62") (name "unconnected-(IC19M-MGTRXP1_267-PadAG22)") (class "Default")
      (node (ref "IC19") (pin "AG22") (pinfunction "MGTRXP1_267_AG22") (pintype "input+no_connect"))
    )
    (net (code "63") (name "unconnected-(IC19M-MGTTXN1_267-PadAK23)") (class "Default")
      (node (ref "IC19") (pin "AK23") (pinfunction "MGTTXN1_267_AK23") (pintype "output"))
    )
    (net (code "64") (name "unconnected-(IC19M-MGTTXP1_267-PadAJ23)") (class "Default")
      (node (ref "IC19") (pin "AJ23") (pinfunction "MGTTXP1_267_AJ23") (pintype "output"))
    )
  )
)
